# Famicon_IO_Jack_Spacer.net
KiCad netlist of a schematic drawn in EAGLE
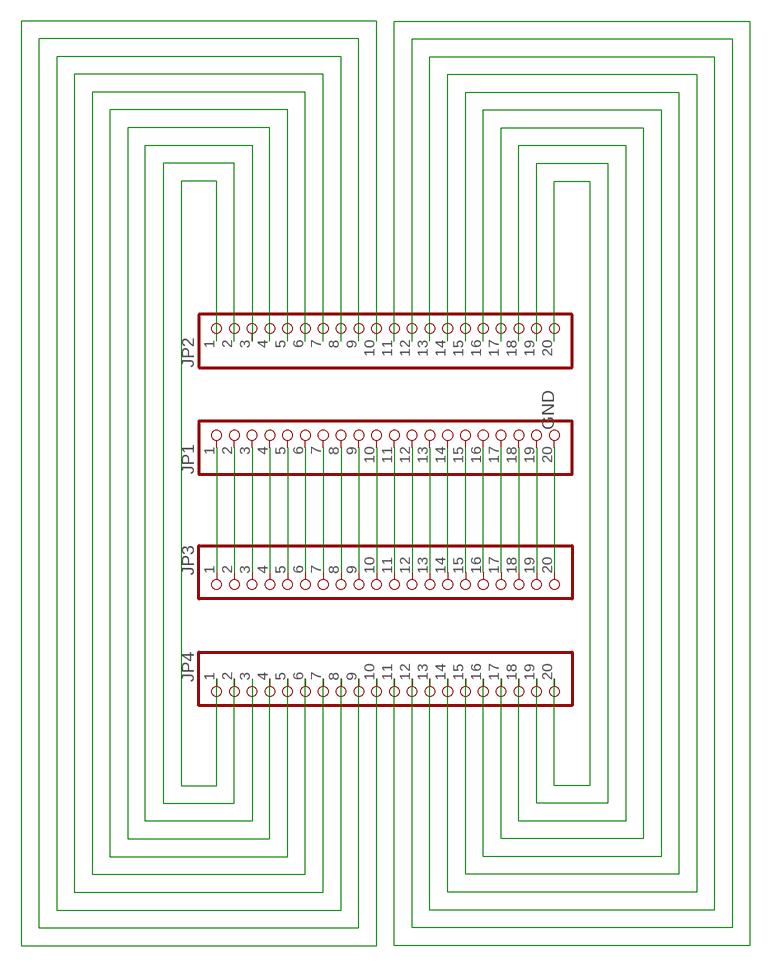
[diagram p0: schematic, sheet 1]

(export (version "E")
  (design (tool "Eeschema 10.0.6"))
  (components
    (comp (ref "JP1")
      (value "PINHD-1X20_2.54-S")
      (footprint "eagle-import:1X20-S")
      (libsource (lib "eagle-import") (part "PINHD-1X20_2.54-S"))
    )
    (comp (ref "JP2")
      (value "PINHD-1X20_2.54-S")
      (footprint "eagle-import:1X20-S")
      (libsource (lib "eagle-import") (part "PINHD-1X20_2.54-S"))
    )
    (comp (ref "JP3")
      (value "PINHD-1X20_2.54-S")
      (footprint "eagle-import:1X20-S")
      (libsource (lib "eagle-import") (part "PINHD-1X20_2.54-S"))
    )
    (comp (ref "JP4")
      (value "PINHD-1X20_2.54-S")
      (footprint "eagle-import:1X20-S")
      (libsource (lib "eagle-import") (part "PINHD-1X20_2.54-S"))
    )
  )
  (nets
    (net (code "1") (name "/GND") (class "Default")
      (node (ref "JP1") (pin "20") (pinfunction "20_20") (pintype "passive"))
      (node (ref "JP3") (pin "20") (pinfunction "20_20") (pintype "passive"))
    )
    (net (code "2") (name "Net-(JP1-Pad1)") (class "Default")
      (node (ref "JP1") (pin "1") (pinfunction "1_1") (pintype "passive"))
      (node (ref "JP3") (pin "1") (pinfunction "1_1") (pintype "passive"))
    )
    (net (code "3") (name "Net-(JP1-Pad2)") (class "Default")
      (node (ref "JP1") (pin "2") (pinfunction "2_2") (pintype "passive"))
      (node (ref "JP3") (pin "2") (pinfunction "2_2") (pintype "passive"))
    )
    (net (code "4") (name "Net-(JP1-Pad3)") (class "Default")
      (node (ref "JP1") (pin "3") (pinfunction "3_3") (pintype "passive"))
      (node (ref "JP3") (pin "3") (pinfunction "3_3") (pintype "passive"))
    )
    (net (code "5") (name "Net-(JP1-Pad4)") (class "Default")
      (node (ref "JP1") (pin "4") (pinfunction "4_4") (pintype "passive"))
      (node (ref "JP3") (pin "4") (pinfunction "4_4") (pintype "passive"))
    )
    (net (code "6") (name "Net-(JP1-Pad5)") (class "Default")
      (node (ref "JP1") (pin "5") (pinfunction "5_5") (pintype "passive"))
      (node (ref "JP3") (pin "5") (pinfunction "5_5") (pintype "passive"))
    )
    (net (code "7") (name "Net-(JP1-Pad6)") (class "Default")
      (node (ref "JP1") (pin "6") (pinfunction "6_6") (pintype "passive"))
      (node (ref "JP3") (pin "6") (pinfunction "6_6") (pintype "passive"))
    )
    (net (code "8") (name "Net-(JP1-Pad7)") (class "Default")
      (node (ref "JP1") (pin "7") (pinfunction "7_7") (pintype "passive"))
      (node (ref "JP3") (pin "7") (pinfunction "7_7") (pintype "passive"))
    )
    (net (code "9") (name "Net-(JP1-Pad8)") (class "Default")
      (node (ref "JP1") (pin "8") (pinfunction "8_8") (pintype "passive"))
      (node (ref "JP3") (pin "8") (pinfunction "8_8") (pintype "passive"))
    )
    (net (code "10") (name "Net-(JP1-Pad9)") (class "Default")
      (node (ref "JP1") (pin "9") (pinfunction "9_9") (pintype "passive"))
      (node (ref "JP3") (pin "9") (pinfunction "9_9") (pintype "passive"))
    )
    (net (code "11") (name "Net-(JP1-Pad10)") (class "Default")
      (node (ref "JP1") (pin "10") (pinfunction "10_10") (pintype "passive"))
      (node (ref "JP3") (pin "10") (pinfunction "10_10") (pintype "passive"))
    )
    (net (code "12") (name "Net-(JP1-Pad11)") (class "Default")
      (node (ref "JP1") (pin "11") (pinfunction "11_11") (pintype "passive"))
      (node (ref "JP3") (pin "11") (pinfunction "11_11") (pintype "passive"))
    )
    (net (code "13") (name "Net-(JP1-Pad12)") (class "Default")
      (node (ref "JP1") (pin "12") (pinfunction "12_12") (pintype "passive"))
      (node (ref "JP3") (pin "12") (pinfunction "12_12") (pintype "passive"))
    )
    (net (code "14") (name "Net-(JP1-Pad13)") (class "Default")
      (node (ref "JP1") (pin "13") (pinfunction "13_13") (pintype "passive"))
      (node (ref "JP3") (pin "13") (pinfunction "13_13") (pintype "passive"))
    )
    (net (code "15") (name "Net-(JP1-Pad14)") (class "Default")
      (node (ref "JP1") (pin "14") (pinfunction "14_14") (pintype "passive"))
      (node (ref "JP3") (pin "14") (pinfunction "14_14") (pintype "passive"))
    )
    (net (code "16") (name "Net-(JP1-Pad15)") (class "Default")
      (node (ref "JP1") (pin "15") (pinfunction "15_15") (pintype "passive"))
      (node (ref "JP3") (pin "15") (pinfunction "15_15") (pintype "passive"))
    )
    (net (code "17") (name "Net-(JP1-Pad16)") (class "Default")
      (node (ref "JP1") (pin "16") (pinfunction "16_16") (pintype "passive"))
      (node (ref "JP3") (pin "16") (pinfunction "16_16") (pintype "passive"))
    )
    (net (code "18") (name "Net-(JP1-Pad17)") (class "Default")
      (node (ref "JP1") (pin "17") (pinfunction "17_17") (pintype "passive"))
      (node (ref "JP3") (pin "17") (pinfunction "17_17") (pintype "passive"))
    )
    (net (code "19") (name "Net-(JP1-Pad18)") (class "Default")
      (node (ref "JP1") (pin "18") (pinfunction "18_18") (pintype "passive"))
      (node (ref "JP3") (pin "18") (pinfunction "18_18") (pintype "passive"))
    )
    (net (code "20") (name "Net-(JP1-Pad19)") (class "Default")
      (node (ref "JP1") (pin "19") (pinfunction "19_19") (pintype "passive"))
      (node (ref "JP3") (pin "19") (pinfunction "19_19") (pintype "passive"))
    )
    (net (code "21") (name "Net-(JP2-Pad1)") (class "Default")
      (node (ref "JP2") (pin "1") (pinfunction "1_1") (pintype "passive"))
      (node (ref "JP4") (pin "1") (pinfunction "1_1") (pintype "passive"))
    )
    (net (code "22") (name "Net-(JP2-Pad2)") (class "Default")
      (node (ref "JP2") (pin "2") (pinfunction "2_2") (pintype "passive"))
      (node (ref "JP4") (pin "2") (pinfunction "2_2") (pintype "passive"))
    )
    (net (code "23") (name "Net-(JP2-Pad3)") (class "Default")
      (node (ref "JP2") (pin "3") (pinfunction "3_3") (pintype "passive"))
      (node (ref "JP4") (pin "3") (pinfunction "3_3") (pintype "passive"))
    )
    (net (code "24") (name "Net-(JP2-Pad4)") (class "Default")
      (node (ref "JP2") (pin "4") (pinfunction "4_4") (pintype "passive"))
      (node (ref "JP4") (pin "4") (pinfunction "4_4") (pintype "passive"))
    )
    (net (code "25") (name "Net-(JP2-Pad5)") (class "Default")
      (node (ref "JP2") (pin "5") (pinfunction "5_5") (pintype "passive"))
      (node (ref "JP4") (pin "5") (pinfunction "5_5") (pintype "passive"))
    )
    (net (code "26") (name "Net-(JP2-Pad6)") (class "Default")
      (node (ref "JP2") (pin "6") (pinfunction "6_6") (pintype "passive"))
      (node (ref "JP4") (pin "6") (pinfunction "6_6") (pintype "passive"))
    )
    (net (code "27") (name "Net-(JP2-Pad7)") (class "Default")
      (node (ref "JP2") (pin "7") (pinfunction "7_7") (pintype "passive"))
      (node (ref "JP4") (pin "7") (pinfunction "7_7") (pintype "passive"))
    )
    (net (code "28") (name "Net-(JP2-Pad8)") (class "Default")
      (node (ref "JP2") (pin "8") (pinfunction "8_8") (pintype "passive"))
      (node (ref "JP4") (pin "8") (pinfunction "8_8") (pintype "passive"))
    )
    (net (code "29") (name "Net-(JP2-Pad9)") (class "Default")
      (node (ref "JP2") (pin "9") (pinfunction "9_9") (pintype "passive"))
      (node (ref "JP4") (pin "9") (pinfunction "9_9") (pintype "passive"))
    )
    (net (code "30") (name "Net-(JP2-Pad10)") (class "Default")
      (node (ref "JP2") (pin "10") (pinfunction "10_10") (pintype "passive"))
      (node (ref "JP4") (pin "10") (pinfunction "10_10") (pintype "passive"))
    )
    (net (code "31") (name "Net-(JP2-Pad11)") (class "Default")
      (node (ref "JP2") (pin "11") (pinfunction "11_11") (pintype "passive"))
      (node (ref "JP4") (pin "11") (pinfunction "11_11") (pintype "passive"))
    )
    (net (code "32") (name "Net-(JP2-Pad12)") (class "Default")
      (node (ref "JP2") (pin "12") (pinfunction "12_12") (pintype "passive"))
      (node (ref "JP4") (pin "12") (pinfunction "12_12") (pintype "passive"))
    )
    (net (code "33") (name "Net-(JP2-Pad13)") (class "Default")
      (node (ref "JP2") (pin "13") (pinfunction "13_13") (pintype "passive"))
      (node (ref "JP4") (pin "13") (pinfunction "13_13") (pintype "passive"))
    )
    (net (code "34") (name "Net-(JP2-Pad14)") (class "Default")
      (node (ref "JP2") (pin "14") (pinfunction "14_14") (pintype "passive"))
      (node (ref "JP4") (pin "14") (pinfunction "14_14") (pintype "passive"))
    )
    (net (code "35") (name "Net-(JP2-Pad15)") (class "Default")
      (node (ref "JP2") (pin "15") (pinfunction "15_15") (pintype "passive"))
      (node (ref "JP4") (pin "15") (pinfunction "15_15") (pintype "passive"))
    )
    (net (code "36") (name "Net-(JP2-Pad16)") (class "Default")
      (node (ref "JP2") (pin "16") (pinfunction "16_16") (pintype "passive"))
      (node (ref "JP4") (pin "16") (pinfunction "16_16") (pintype "passive"))
    )
    (net (code "37") (name "Net-(JP2-Pad17)") (class "Default")
      (node (ref "JP2") (pin "17") (pinfunction "17_17") (pintype "passive"))
      (node (ref "JP4") (pin "17") (pinfunction "17_17") (pintype "passive"))
    )
    (net (code "38") (name "Net-(JP2-Pad18)") (class "Default")
      (node (ref "JP2") (pin "18") (pinfunction "18_18") (pintype "passive"))
      (node (ref "JP4") (pin "18") (pinfunction "18_18") (pintype "passive"))
    )
    (net (code "39") (name "Net-(JP2-Pad19)") (class "Default")
      (node (ref "JP2") (pin "19") (pinfunction "19_19") (pintype "passive"))
      (node (ref "JP4") (pin "19") (pinfunction "19_19") (pintype "passive"))
    )
    (net (code "40") (name "Net-(JP2-Pad20)") (class "Default")
      (node (ref "JP2") (pin "20") (pinfunction "20_20") (pintype "passive"))
      (node (ref "JP4") (pin "20") (pinfunction "20_20") (pintype "passive"))
    )
  )
)
